# MCU.net
KiCad netlist of a schematic drawn in Altium Designer
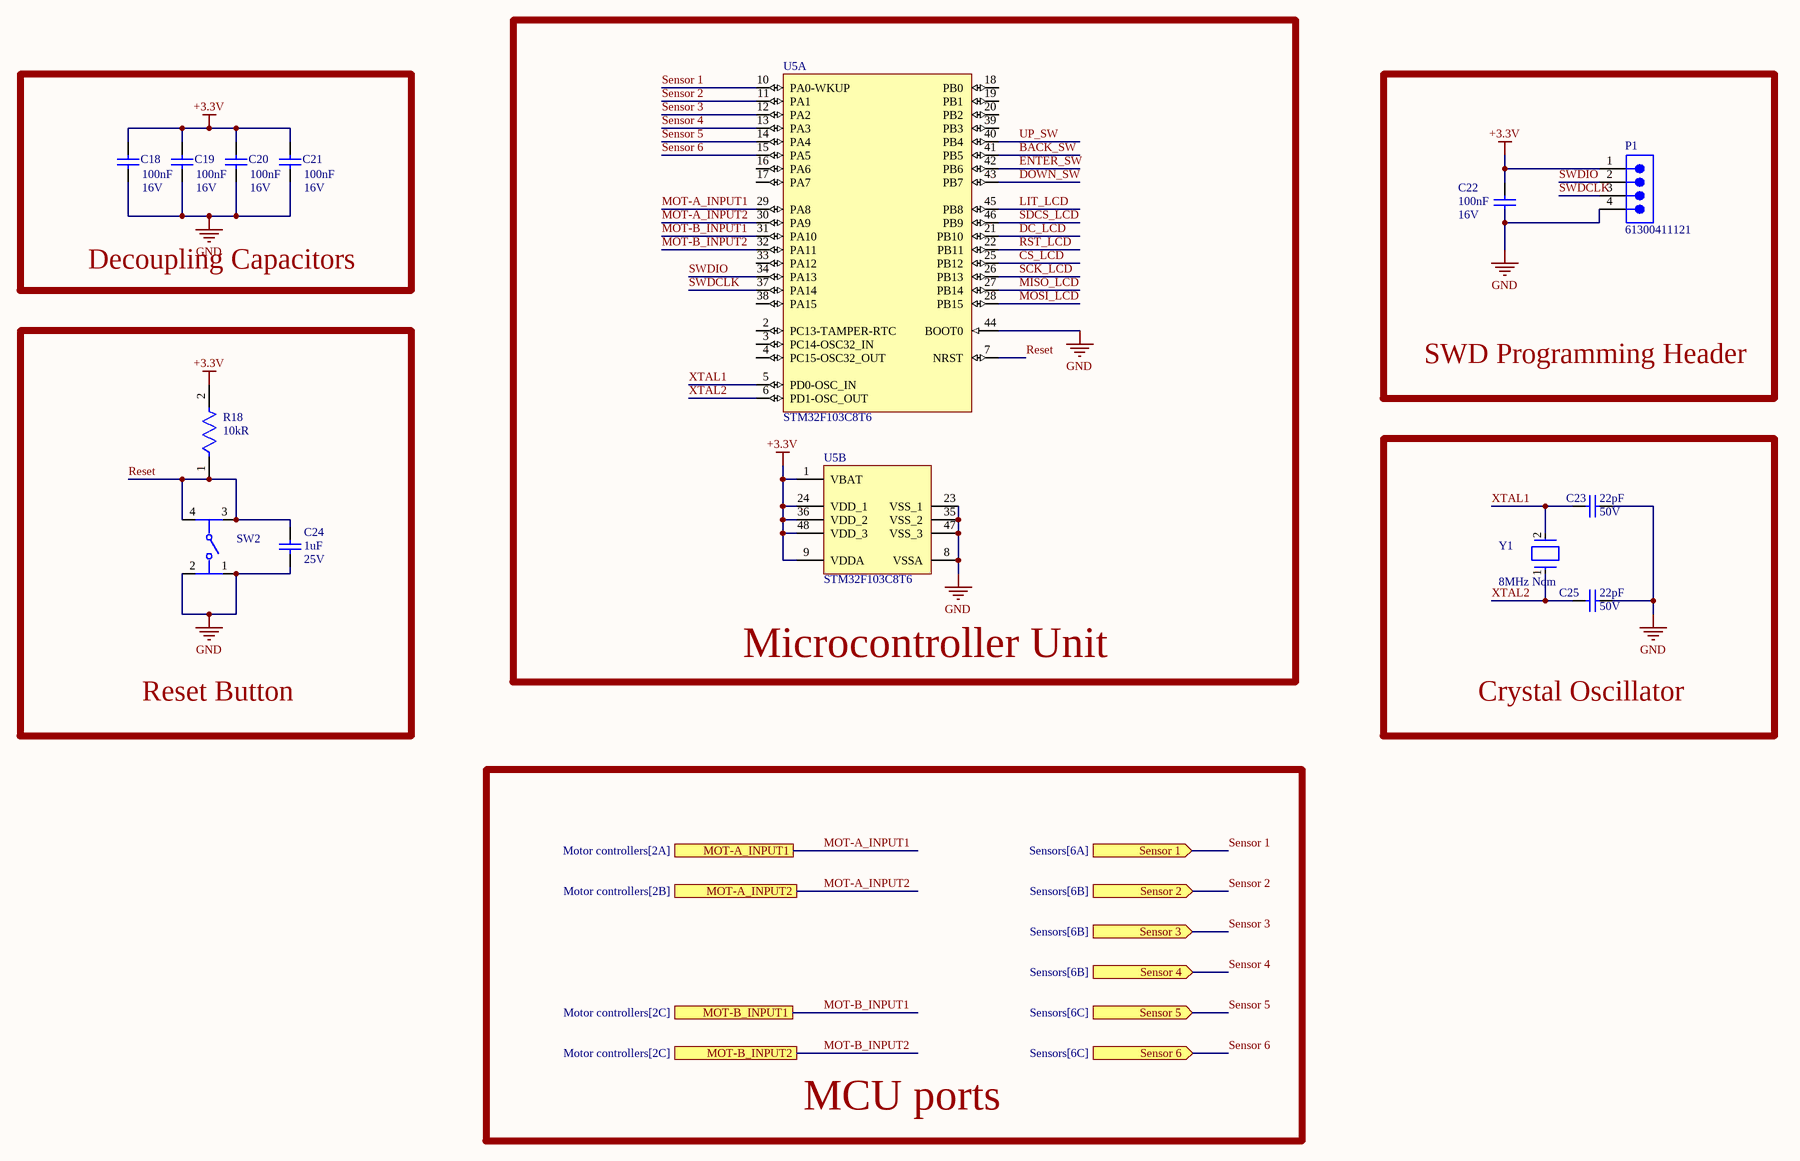
[diagram p0: MCU.SchDoc]

(export (version "E")
  (design (tool "Eeschema 10.0.6"))
  (components
    (comp (ref "C18")
      (value "100nF")
      (footprint "CAPC1608X90X35LL15T15")
      (fields (field (name "RATED DC VOLTAGE (URDC)") "16V") (field (name "Comment") "0.1uF 16V 0603"))
      (libsource (lib "2025 Bright Manufacturing Challenge") (part "CAP"))
    )
    (comp (ref "C19")
      (value "100nF")
      (footprint "CAPC1608X90X35LL15T15")
      (fields (field (name "RATED DC VOLTAGE (URDC)") "16V") (field (name "Comment") "0.1uF 16V 0603"))
      (libsource (lib "2025 Bright Manufacturing Challenge") (part "CAP"))
    )
    (comp (ref "C20")
      (value "100nF")
      (footprint "CAPC1608X90X35LL15T15")
      (fields (field (name "RATED DC VOLTAGE (URDC)") "16V") (field (name "Comment") "0.1uF 16V 0603"))
      (libsource (lib "2025 Bright Manufacturing Challenge") (part "CAP"))
    )
    (comp (ref "C21")
      (value "100nF")
      (footprint "CAPC1608X90X35LL15T15")
      (fields (field (name "RATED DC VOLTAGE (URDC)") "16V") (field (name "Comment") "0.1uF 16V 0603"))
      (libsource (lib "2025 Bright Manufacturing Challenge") (part "CAP"))
    )
    (comp (ref "C22")
      (value "100nF")
      (footprint "CAPC1608X90X35LL15T15")
      (fields (field (name "RATED DC VOLTAGE (URDC)") "16V") (field (name "Comment") "0.1uF 16V 0603"))
      (libsource (lib "2025 Bright Manufacturing Challenge") (part "CAP"))
    )
    (comp (ref "C23")
      (value "22pF")
      (footprint "FP-C0603C-CF-IPC_B")
      (fields (field (name "VOLTAGE RATING") "50V") (field (name "Comment") "22pF 50V 0603"))
      (libsource (lib "2025 Bright Manufacturing Challenge") (part "CAP"))
    )
    (comp (ref "C24")
      (value "1uF")
      (footprint "FP-CC0603-DA-IPC_B")
      (fields (field (name "RATED DC VOLTAGE (URDC)") "25V") (field (name "Comment") "1uF 25V 0603"))
      (libsource (lib "2025 Bright Manufacturing Challenge") (part "CAP"))
    )
    (comp (ref "C25")
      (value "22pF")
      (footprint "FP-C0603C-CF-IPC_B")
      (fields (field (name "VOLTAGE RATING") "50V") (field (name "Comment") "22pF 50V 0603"))
      (libsource (lib "2025 Bright Manufacturing Challenge") (part "CAP"))
    )
    (comp (ref "P1")
      (value "61300411121")
      (footprint "61300411121")
      (libsource (lib "2025 Bright Manufacturing Challenge") (part "Header_Male_1R_04P"))
    )
    (comp (ref "R18")
      (value "10kR")
      (footprint "RESC1608X55X25ML10T15")
      (fields
        (field (name "TOLERANCE") "5%")
        (field (name "POWER") "100mW")
        (field (name "Comment") "10KOhm 0603")
      )
      (libsource (lib "2025 Bright Manufacturing Challenge") (part "1029c3af85768c4190bb7ad29bc67b5"))
    )
    (comp (ref "SW2")
      (value "PTS645SM43SMTR92LFS")
      (footprint "FP-PTS645SM43SMTR92LFS-MFG")
      (libsource (lib "2025 Bright Manufacturing Challenge") (part "1adf0dd01260c80cf25a44bfd6b99ba"))
    )
    (comp (ref "U5")
      (value "STM32F103C8T6")
      (footprint "STM-LQFP48_M")
      (description "RISC Microcontroller, 32-Bit, FLASH, STM32 CPU, 72MHz, CMOS, PQFP48")
      (libsource (lib "2025 Bright Manufacturing Challenge") (part "MC-ARM-STM32F103X8_B-SQ48"))
    )
    (comp (ref "Y1")
      (value "ABLS2-8.000MHZ-D4Y-T")
      (footprint "FP-ABLS2-MFG")
      (description "8MHz Nom")
      (fields (field (name "OPERATING FREQUENCY") "8MHz Nom"))
      (libsource (lib "2025 Bright Manufacturing Challenge") (part "c23a69dc6c9e2f18f2079038eb95dd1"))
    )
  )
  (nets
    (net (code "1") (name "+3.3V") (class "Default")
      (node (ref "C18") (pin "2") (pinfunction "2_2") (pintype "passive"))
      (node (ref "C19") (pin "2") (pinfunction "2_2") (pintype "passive"))
      (node (ref "C20") (pin "2") (pinfunction "2_2") (pintype "passive"))
      (node (ref "C21") (pin "2") (pinfunction "2_2") (pintype "passive"))
      (node (ref "C22") (pin "2") (pinfunction "2_2") (pintype "passive"))
      (node (ref "P1") (pin "1") (pinfunction "1_1") (pintype "passive"))
      (node (ref "R18") (pin "2") (pinfunction "2_2") (pintype "passive"))
      (node (ref "U5") (pin "1") (pinfunction "VBAT_1") (pintype "power_in"))
      (node (ref "U5") (pin "24") (pinfunction "VDD_1_24") (pintype "power_in"))
      (node (ref "U5") (pin "36") (pinfunction "VDD_2_36") (pintype "power_in"))
      (node (ref "U5") (pin "48") (pinfunction "VDD_3_48") (pintype "power_in"))
      (node (ref "U5") (pin "9") (pinfunction "VDDA_9") (pintype "power_in"))
    )
    (net (code "2") (name "/BACK_SW") (class "Default")
      (node (ref "U5") (pin "41") (pinfunction "PB5_41") (pintype "bidirectional"))
    )
    (net (code "3") (name "/CS_LCD") (class "Default")
      (node (ref "U5") (pin "25") (pinfunction "PB12_25") (pintype "bidirectional"))
    )
    (net (code "4") (name "/DC_LCD") (class "Default")
      (node (ref "U5") (pin "21") (pinfunction "PB10_21") (pintype "bidirectional"))
    )
    (net (code "5") (name "/DOWN_SW") (class "Default")
      (node (ref "U5") (pin "43") (pinfunction "PB7_43") (pintype "bidirectional"))
    )
    (net (code "6") (name "/ENTER_SW") (class "Default")
      (node (ref "U5") (pin "42") (pinfunction "PB6_42") (pintype "bidirectional"))
    )
    (net (code "7") (name "/LIT_LCD") (class "Default")
      (node (ref "U5") (pin "45") (pinfunction "PB8_45") (pintype "bidirectional"))
    )
    (net (code "8") (name "/MISO_LCD") (class "Default")
      (node (ref "U5") (pin "27") (pinfunction "PB14_27") (pintype "bidirectional"))
    )
    (net (code "9") (name "/MOSI_LCD") (class "Default")
      (node (ref "U5") (pin "28") (pinfunction "PB15_28") (pintype "bidirectional"))
    )
    (net (code "10") (name "/MOT-A_INPUT1") (class "Default")
      (node (ref "U5") (pin "29") (pinfunction "PA8_29") (pintype "bidirectional"))
    )
    (net (code "11") (name "/MOT-A_INPUT2") (class "Default")
      (node (ref "U5") (pin "30") (pinfunction "PA9_30") (pintype "bidirectional"))
    )
    (net (code "12") (name "/MOT-B_INPUT1") (class "Default")
      (node (ref "U5") (pin "31") (pinfunction "PA10_31") (pintype "bidirectional"))
    )
    (net (code "13") (name "/MOT-B_INPUT2") (class "Default")
      (node (ref "U5") (pin "32") (pinfunction "PA11_32") (pintype "bidirectional"))
    )
    (net (code "14") (name "/RST_LCD") (class "Default")
      (node (ref "U5") (pin "22") (pinfunction "PB11_22") (pintype "bidirectional"))
    )
    (net (code "15") (name "/Reset") (class "Default")
      (node (ref "C24") (pin "2") (pinfunction "2_2") (pintype "passive"))
      (node (ref "R18") (pin "1") (pinfunction "1_1") (pintype "passive"))
      (node (ref "SW2") (pin "3") (pinfunction "3_3") (pintype "passive"))
      (node (ref "SW2") (pin "4") (pinfunction "4_4") (pintype "passive"))
      (node (ref "U5") (pin "7") (pinfunction "NRST_7") (pintype "bidirectional"))
    )
    (net (code "16") (name "/SCK_LCD") (class "Default")
      (node (ref "U5") (pin "26") (pinfunction "PB13_26") (pintype "bidirectional"))
    )
    (net (code "17") (name "/SDCS_LCD") (class "Default")
      (node (ref "U5") (pin "46") (pinfunction "PB9_46") (pintype "bidirectional"))
    )
    (net (code "18") (name "/SWDCLK") (class "Default")
      (node (ref "P1") (pin "3") (pinfunction "3_3") (pintype "passive"))
      (node (ref "U5") (pin "37") (pinfunction "PA14_37") (pintype "bidirectional"))
    )
    (net (code "19") (name "/SWDIO") (class "Default")
      (node (ref "P1") (pin "2") (pinfunction "2_2") (pintype "passive"))
      (node (ref "U5") (pin "34") (pinfunction "PA13_34") (pintype "bidirectional"))
    )
    (net (code "20") (name "/Sensor 1") (class "Default")
      (node (ref "U5") (pin "10") (pinfunction "PA0-WKUP_10") (pintype "bidirectional"))
    )
    (net (code "21") (name "/Sensor 2") (class "Default")
      (node (ref "U5") (pin "11") (pinfunction "PA1_11") (pintype "bidirectional"))
    )
    (net (code "22") (name "/Sensor 3") (class "Default")
      (node (ref "U5") (pin "12") (pinfunction "PA2_12") (pintype "bidirectional"))
    )
    (net (code "23") (name "/Sensor 4") (class "Default")
      (node (ref "U5") (pin "13") (pinfunction "PA3_13") (pintype "bidirectional"))
    )
    (net (code "24") (name "/Sensor 5") (class "Default")
      (node (ref "U5") (pin "14") (pinfunction "PA4_14") (pintype "bidirectional"))
    )
    (net (code "25") (name "/Sensor 6") (class "Default")
      (node (ref "U5") (pin "15") (pinfunction "PA5_15") (pintype "bidirectional"))
    )
    (net (code "26") (name "/UP_SW") (class "Default")
      (node (ref "U5") (pin "40") (pinfunction "PB4_40") (pintype "bidirectional"))
    )
    (net (code "27") (name "/XTAL1") (class "Default")
      (node (ref "C23") (pin "2") (pinfunction "2_2") (pintype "passive"))
      (node (ref "U5") (pin "5") (pinfunction "PD0-OSC_IN_5") (pintype "bidirectional"))
      (node (ref "Y1") (pin "2") (pinfunction "2_2") (pintype "passive"))
    )
    (net (code "28") (name "/XTAL2") (class "Default")
      (node (ref "C25") (pin "2") (pinfunction "2_2") (pintype "passive"))
      (node (ref "U5") (pin "6") (pinfunction "PD1-OSC_OUT_6") (pintype "bidirectional"))
      (node (ref "Y1") (pin "1") (pinfunction "1_1") (pintype "passive"))
    )
    (net (code "29") (name "GND") (class "Default")
      (node (ref "C18") (pin "1") (pinfunction "1_1") (pintype "passive"))
      (node (ref "C19") (pin "1") (pinfunction "1_1") (pintype "passive"))
      (node (ref "C20") (pin "1") (pinfunction "1_1") (pintype "passive"))
      (node (ref "C21") (pin "1") (pinfunction "1_1") (pintype "passive"))
      (node (ref "C22") (pin "1") (pinfunction "1_1") (pintype "passive"))
      (node (ref "C23") (pin "1") (pinfunction "1_1") (pintype "passive"))
      (node (ref "C24") (pin "1") (pinfunction "1_1") (pintype "passive"))
      (node (ref "C25") (pin "1") (pinfunction "1_1") (pintype "passive"))
      (node (ref "P1") (pin "4") (pinfunction "4_4") (pintype "passive"))
      (node (ref "SW2") (pin "1") (pinfunction "1_1") (pintype "passive"))
      (node (ref "SW2") (pin "2") (pinfunction "2_2") (pintype "passive"))
      (node (ref "U5") (pin "23") (pinfunction "VSS_1_23") (pintype "power_in"))
      (node (ref "U5") (pin "35") (pinfunction "VSS_2_35") (pintype "power_in"))
      (node (ref "U5") (pin "44") (pinfunction "BOOT0_44") (pintype "input"))
      (node (ref "U5") (pin "47") (pinfunction "VSS_3_47") (pintype "power_in"))
      (node (ref "U5") (pin "8") (pinfunction "VSSA_8") (pintype "power_in"))
    )
    (net (code "30") (name "unconnected-(U5A-PA6-Pad16)") (class "Default")
      (node (ref "U5") (pin "16") (pinfunction "PA6_16") (pintype "bidirectional"))
    )
    (net (code "31") (name "unconnected-(U5A-PA7-Pad17)") (class "Default")
      (node (ref "U5") (pin "17") (pinfunction "PA7_17") (pintype "bidirectional"))
    )
    (net (code "32") (name "unconnected-(U5A-PA12-Pad33)") (class "Default")
      (node (ref "U5") (pin "33") (pinfunction "PA12_33") (pintype "bidirectional"))
    )
    (net (code "33") (name "unconnected-(U5A-PA15-Pad38)") (class "Default")
      (node (ref "U5") (pin "38") (pinfunction "PA15_38") (pintype "bidirectional"))
    )
    (net (code "34") (name "unconnected-(U5A-PB0-Pad18)") (class "Default")
      (node (ref "U5") (pin "18") (pinfunction "PB0_18") (pintype "bidirectional"))
    )
    (net (code "35") (name "unconnected-(U5A-PB1-Pad19)") (class "Default")
      (node (ref "U5") (pin "19") (pinfunction "PB1_19") (pintype "bidirectional"))
    )
    (net (code "36") (name "unconnected-(U5A-PB2-Pad20)") (class "Default")
      (node (ref "U5") (pin "20") (pinfunction "PB2_20") (pintype "bidirectional"))
    )
    (net (code "37") (name "unconnected-(U5A-PB3-Pad39)") (class "Default")
      (node (ref "U5") (pin "39") (pinfunction "PB3_39") (pintype "bidirectional"))
    )
    (net (code "38") (name "unconnected-(U5A-PC13-TAMPER-RTC-Pad2)") (class "Default")
      (node (ref "U5") (pin "2") (pinfunction "PC13-TAMPER-RTC_2") (pintype "bidirectional"))
    )
    (net (code "39") (name "unconnected-(U5A-PC14-OSC32_IN-Pad3)") (class "Default")
      (node (ref "U5") (pin "3") (pinfunction "PC14-OSC32_IN_3") (pintype "bidirectional"))
    )
    (net (code "40") (name "unconnected-(U5A-PC15-OSC32_OUT-Pad4)") (class "Default")
      (node (ref "U5") (pin "4") (pinfunction "PC15-OSC32_OUT_4") (pintype "bidirectional"))
    )
  )
)
